# Main.net
KiCad netlist of a schematic drawn in Altium Designer
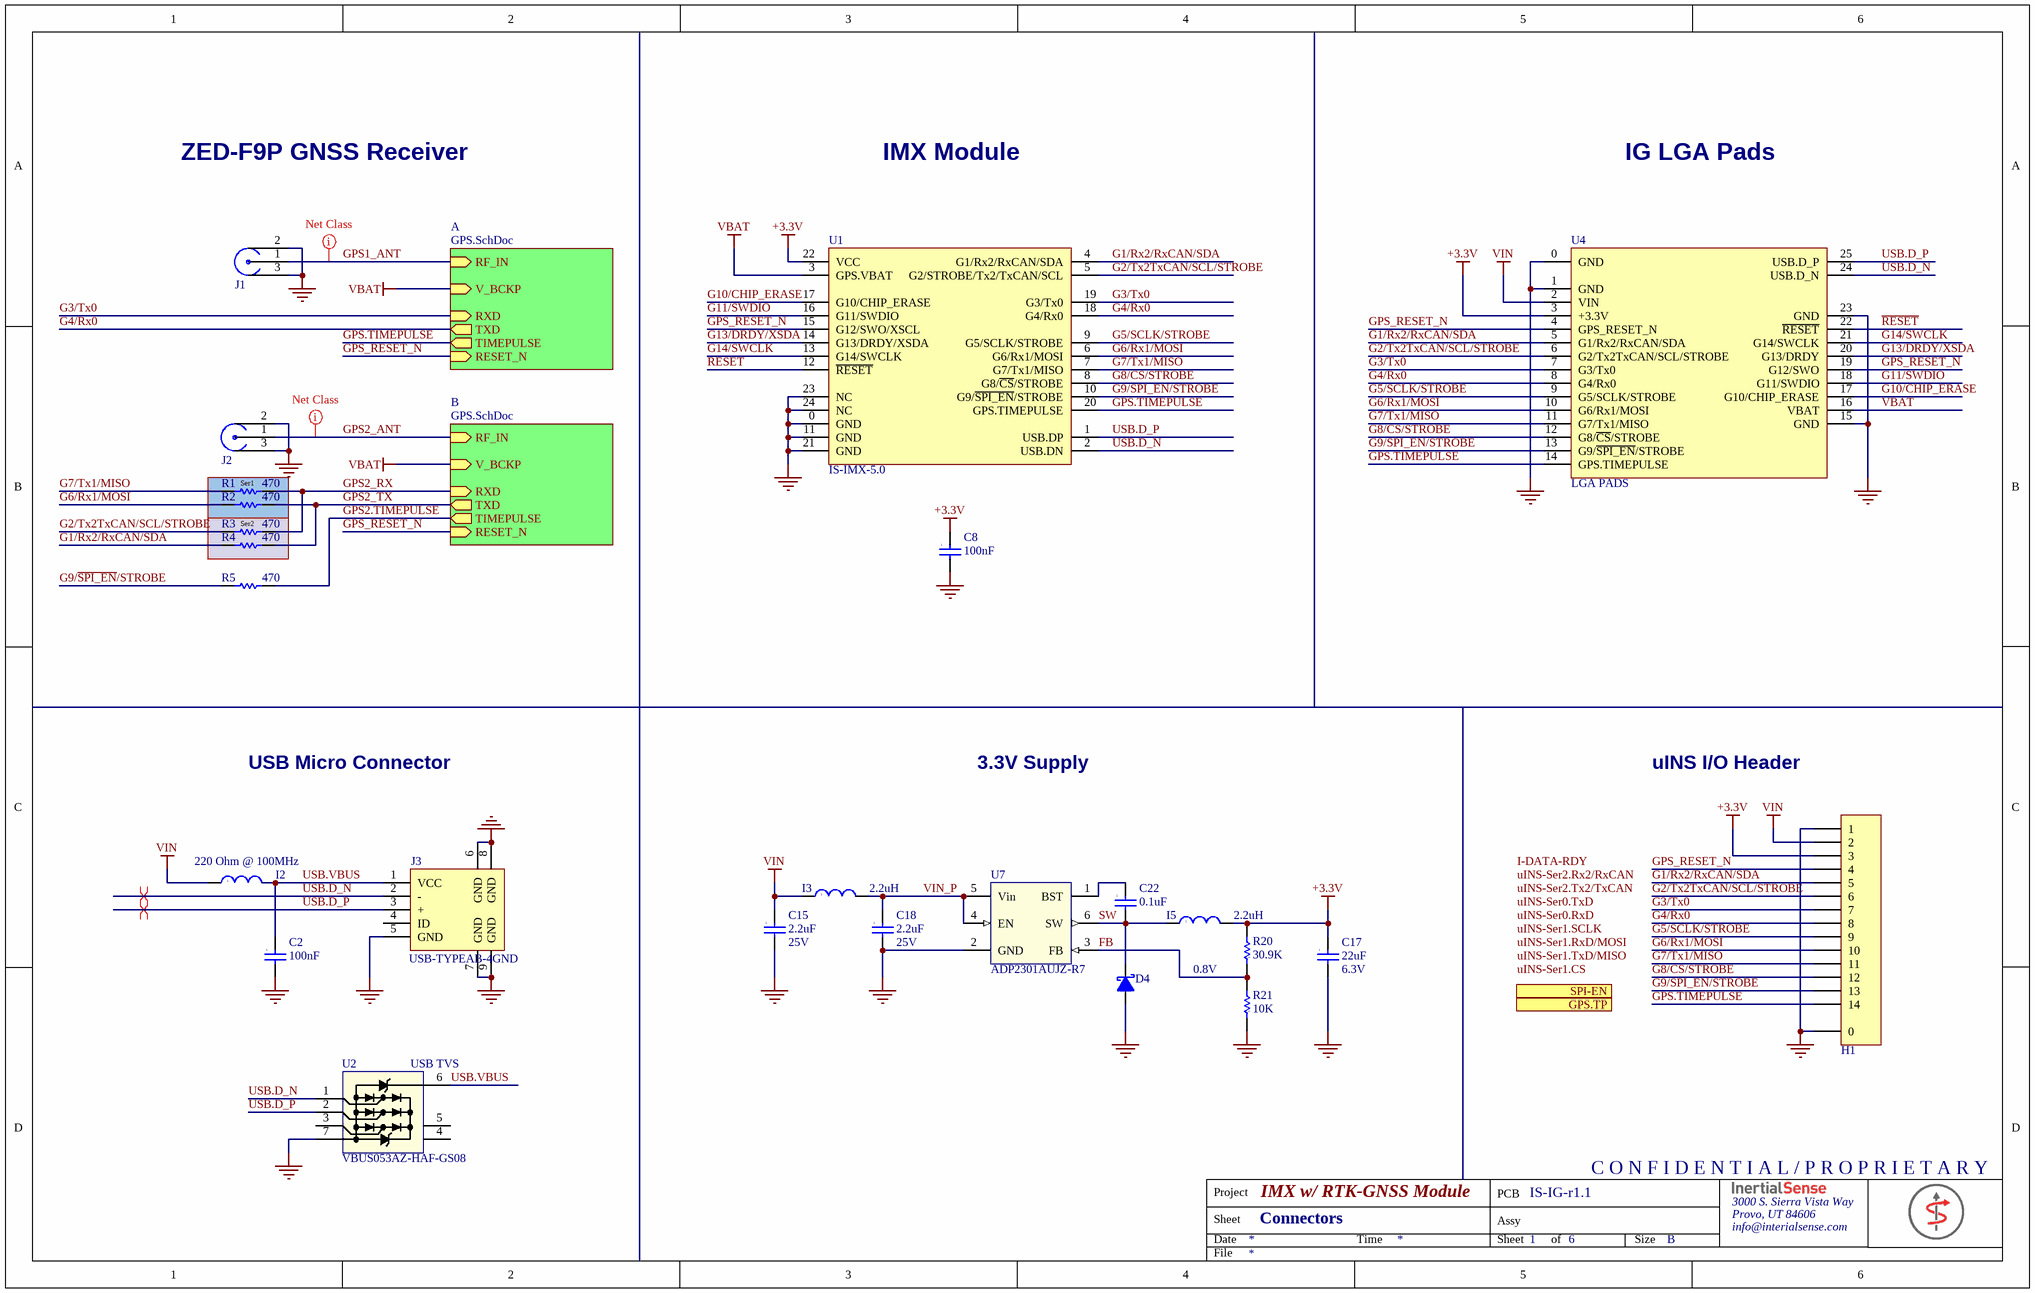
[diagram p0: Main.SchDoc]

(export (version "E")
  (design (tool "Eeschema 10.0.6"))
  (components
    (comp (ref "C2")
      (value "100nF")
      (footprint "0402")
      (description "CAP CER .10UF 50V X7R 10% 0402")
      (fields
        (field (name "MANUFACTURER") "TDK Corporation")
        (field (name "MANUFACTURER PART NUMBER") "C1005X7R1H104K")
        (field (name "PUBLISHER") "Altium Limited")
      )
      (libsource (lib "General") (part "Cap"))
    )
    (comp (ref "C8")
      (value "100nF")
      (footprint "0402")
      (description "CAP CER .10UF 50V X7R 10% 0402")
      (fields
        (field (name "MANUFACTURER") "TDK Corporation")
        (field (name "MANUFACTURER PART NUMBER") "C1005X7R1H104K")
        (field (name "PUBLISHER") "Altium Limited")
      )
      (libsource (lib "General") (part "Cap"))
    )
    (comp (ref "C15")
      (value "2.2uF")
      (footprint "0603")
      (description "CAP CER 2.2UF 25V X6S 0603")
      (fields
        (field (name "MANUFACTURER") "Murata")
        (field (name "MANUFACTURER PART NUMBER") "GRT188C81E225KE13D")
        (field (name "VOLTAGE RATING") "25V")
        (field (name "PUBLISHER") "Altium Limited")
      )
      (libsource (lib "") (part "Cap_1"))
    )
    (comp (ref "C17")
      (value "22uF")
      (footprint "0603")
      (description "CAP CER 22UF 6.3V X6S 0603")
      (fields
        (field (name "MANUFACTURER") "Murata")
        (field (name "MANUFACTURER PART NUMBER") "GRM188C80J226ME15D")
        (field (name "VOLTAGE RATING") "6.3V")
        (field (name "PUBLISHER") "Altium Limited")
      )
      (libsource (lib "") (part "Cap_1"))
    )
    (comp (ref "C18")
      (value "2.2uF")
      (footprint "0603")
      (description "CAP CER 2.2UF 25V X6S 0603")
      (fields
        (field (name "MANUFACTURER") "Murata")
        (field (name "MANUFACTURER PART NUMBER") "GRT188C81E225KE13D")
        (field (name "VOLTAGE RATING") "25V")
        (field (name "PUBLISHER") "Altium Limited")
      )
      (libsource (lib "") (part "Cap_1"))
    )
    (comp (ref "C22")
      (value "0.1uF")
      (footprint "0402")
      (description "CAP CER 0.1UF 50V X7R 0402")
      (fields
        (field (name "MANUFACTURER") "TDK")
        (field (name "MANUFACTURER PART NUMBER") "CGA2B3X7R1H104K050BB")
        (field (name "PUBLISHER") "Altium Limited")
      )
      (libsource (lib "") (part "Cap_1"))
    )
    (comp (ref "D4")
      (value "Diode - Schottky")
      (footprint "D0603B")
      (description "DIODE SCHOTTKY 30V 2A 0603")
      (fields
        (field (name "MANUFACTURER") "Vishay")
        (field (name "MANUFACTURER PART NUMBER") "VSKY20301608-G4-08")
      )
      (libsource (lib "General") (part "Diode - Schottky"))
    )
    (comp (ref "H1")
      (value "Hdr - 14pin - mount")
      (footprint "SM14B-GHS-TB(LF)(SN)")
      (description "Conn Shrouded Header HDR 14 POS 1.25mm Solder ST Top Entry SMD T/R")
      (fields
        (field (name "MANUFACTURER") "JST")
        (field (name "MANUFACTURER PART NUMBER") "SM14B-GHS-TB(LF)(SN)")
      )
      (libsource (lib "Connectors") (part "Hdr - 14pin - mount"))
    )
    (comp (ref "I2")
      (value "220 Ohm @ 100MHz")
      (footprint "I0603")
      (description "FERRITE CHIP 220 OHM 2500MA 0603")
      (fields
        (field (name "MANUFACTURER") "Murata Electronics North America")
        (field (name "MANUFACTURER PART NUMBER") "BLM18SG221TN1D")
      )
      (libsource (lib "General") (part "Inductor"))
    )
    (comp (ref "I3")
      (value "2.2uH")
      (footprint "0806")
      (description "FIXED IND 2.2UH 1.2A 110 MOHM")
      (fields
        (field (name "MANUFACTURER") "TDK")
        (field (name "MANUFACTURER PART NUMBER") "MLP2016H2R2MT0S1")
      )
      (libsource (lib "") (part "Inductor_1"))
    )
    (comp (ref "I5")
      (value "2.2uH")
      (footprint "0806")
      (description "FIXED IND 2.2UH 1.2A 110 MOHM")
      (fields
        (field (name "MANUFACTURER") "TDK")
        (field (name "MANUFACTURER PART NUMBER") "MLP2016H2R2MT0S1")
      )
      (libsource (lib "") (part "Inductor_1"))
    )
    (comp (ref "J1")
      (value "RF - GND x 2")
      (footprint "RF UMC SMD")
      (description "CONN UMC RCPT STR 50 OHM SMD")
      (fields
        (field (name "MANUFACTURER") "Emerson Network Power Connectivity Johnson")
        (field (name "MANUFACTURER PART NUMBER") "128-0711-201")
      )
      (libsource (lib "Connectors") (part "RF - GND x 2"))
    )
    (comp (ref "J2")
      (value "RF - GND x 2")
      (footprint "RF UMC SMD")
      (description "CONN UMC RCPT STR 50 OHM SMD")
      (fields
        (field (name "MANUFACTURER") "Emerson Network Power Connectivity Johnson")
        (field (name "MANUFACTURER PART NUMBER") "128-0711-201")
      )
      (libsource (lib "Connectors") (part "RF - GND x 2"))
    )
    (comp (ref "J3")
      (value "USB-TYPEAB-4GND")
      (footprint "USB Micro AB R/A THR")
      (description "CONN USB AB 4POS")
      (fields
        (field (name "MANUFACTURER") "Amphenol FCI")
        (field (name "MANUFACTURER PART NUMBER") "10118194-0001LF")
      )
      (libsource (lib "Connectors") (part "USB-TYPEAB-4GND"))
    )
    (comp (ref "R1")
      (value "470")
      (footprint "R0402")
      (description "RES 470 OHM 1/16W 1% 0402 SMD")
      (fields
        (field (name "MANUFACTURER") "Vishay Dale")
        (field (name "MANUFACTURER PART NUMBER") "CRCW0402470RFKED")
      )
      (libsource (lib "") (part "Res_1"))
    )
    (comp (ref "R2")
      (value "470")
      (footprint "R0402")
      (description "RES 470 OHM 1/16W 1% 0402 SMD")
      (fields
        (field (name "MANUFACTURER") "Vishay Dale")
        (field (name "MANUFACTURER PART NUMBER") "CRCW0402470RFKED")
      )
      (libsource (lib "") (part "Res_1"))
    )
    (comp (ref "R3")
      (value "470")
      (footprint "R0402")
      (description "RES 470 OHM 1/16W 1% 0402 SMD")
      (fields
        (field (name "MANUFACTURER") "Vishay Dale")
        (field (name "MANUFACTURER PART NUMBER") "CRCW0402470RFKED")
      )
      (libsource (lib "") (part "Res_1"))
    )
    (comp (ref "R4")
      (value "470")
      (footprint "R0402")
      (description "RES 470 OHM 1/16W 1% 0402 SMD")
      (fields
        (field (name "MANUFACTURER") "Vishay Dale")
        (field (name "MANUFACTURER PART NUMBER") "CRCW0402470RFKED")
      )
      (libsource (lib "") (part "Res_1"))
    )
    (comp (ref "R5")
      (value "470")
      (footprint "R0402")
      (description "RES 470 OHM 1/16W 1% 0402 SMD")
      (fields
        (field (name "MANUFACTURER") "Vishay Dale")
        (field (name "MANUFACTURER PART NUMBER") "CRCW0402470RFKED")
      )
      (libsource (lib "") (part "Res_1"))
    )
    (comp (ref "R20")
      (value "30.9K")
      (footprint "R0402")
      (description "RES TF 30.9K OHM 1% 1/16W 0402")
      (fields
        (field (name "MANUFACTURER") "Stackpole Electronics Inc")
        (field (name "MANUFACTURER PART NUMBER") "RMCF0402FT30K9")
      )
      (libsource (lib "General") (part "Res"))
    )
    (comp (ref "R21")
      (value "10K")
      (footprint "R0402")
      (description "RES 10.0K OHM 1/16W 1% 0402 SMD")
      (fields
        (field (name "MANUFACTURER") "Yageo")
        (field (name "MANUFACTURER PART NUMBER") "RC0402FR-0710KL")
      )
      (libsource (lib "General") (part "Res"))
    )
    (comp (ref "U1")
      (value "IMX")
      (footprint "IS-IMX-5.0")
      (description "Inertial Sense IMX")
      (fields
        (field (name "MANUFACTURER") "Inertial Sense")
        (field (name "MANUFACTURER PART NUMBER") "IS-IMX-5.0")
      )
      (libsource (lib "IS-IMX-5") (part "IS-IMX-5.0"))
    )
    (comp (ref "U2")
      (value "VBUS053")
      (footprint "QFN50P160X160X60-6N")
      (description "ESD SUPPRESS 5.5V 36W 3-Line USB")
      (fields
        (field (name "MANUFACTURER") "Vishay Semiconductors")
        (field (name "MANUFACTURER PART NUMBER") "VBUS053AZ-HAF-GS08")
      )
      (libsource (lib "ICs") (part "VBUS053"))
    )
    (comp (ref "U4")
      (value "LGA PADS")
      (footprint "IG-1.0_LGA")
      (description "IMX multi-frequency RTK-GNSS Module")
      (libsource (lib "Sensors") (part "IG_1.0_LGA"))
    )
    (comp (ref "U7")
      (value "ADP2301")
      (footprint "MO-178-AB")
      (description "IC BUCK ADJ 1.2A 6TSOT")
      (fields
        (field (name "MANUFACTURER") "Analog Devices Inc")
        (field (name "MANUFACTURER PART NUMBER") "ADP2301AUJZ-R7")
      )
      (libsource (lib "ICs") (part "ADP2301"))
    )
  )
  (nets
    (net (code "1") (name "+3.3V") (class "Default")
      (node (ref "C17") (pin "1") (pinfunction "1_1") (pintype "passive"))
      (node (ref "C8") (pin "1") (pinfunction "1_1") (pintype "passive"))
      (node (ref "H1") (pin "3") (pinfunction "3_3") (pintype "passive"))
      (node (ref "I5") (pin "2") (pinfunction "2_2") (pintype "passive"))
      (node (ref "R20") (pin "2") (pinfunction "2_2") (pintype "passive"))
      (node (ref "U1") (pin "22") (pinfunction "VCC_22") (pintype "power_in"))
      (node (ref "U4") (pin "3") (pinfunction "+3.3V_3") (pintype "passive"))
    )
    (net (code "2") (name "/FB") (class "Default")
      (node (ref "R20") (pin "1") (pinfunction "1_1") (pintype "passive"))
      (node (ref "R21") (pin "2") (pinfunction "2_2") (pintype "passive"))
      (node (ref "U7") (pin "3") (pinfunction "FB_3") (pintype "input"))
    )
    (net (code "3") (name "/G1{slash}Rx2{slash}RxCAN{slash}SDA") (class "Default")
      (node (ref "H1") (pin "5") (pinfunction "5_5") (pintype "passive"))
      (node (ref "R4") (pin "1") (pinfunction "1_1") (pintype "passive"))
      (node (ref "U1") (pin "4") (pinfunction "G1/Rx2/RxCAN/SDA_4") (pintype "passive"))
      (node (ref "U4") (pin "5") (pinfunction "G1/Rx2/RxCAN/SDA_5") (pintype "passive"))
    )
    (net (code "4") (name "/G2{slash}Tx2TxCAN{slash}SCL{slash}STROBE") (class "Default")
      (node (ref "H1") (pin "6") (pinfunction "6_6") (pintype "passive"))
      (node (ref "R3") (pin "1") (pinfunction "1_1") (pintype "passive"))
      (node (ref "U1") (pin "5") (pinfunction "G2/STROBE/Tx2/TxCAN/SCL_5") (pintype "passive"))
      (node (ref "U4") (pin "6") (pinfunction "G2/Tx2TxCAN/SCL/STROBE_6") (pintype "passive"))
    )
    (net (code "5") (name "/G3{slash}Tx0") (class "Default")
      (node (ref "H1") (pin "7") (pinfunction "7_7") (pintype "passive"))
      (node (ref "U1") (pin "19") (pinfunction "G3/Tx0_19") (pintype "passive"))
      (node (ref "U4") (pin "7") (pinfunction "G3/Tx0_7") (pintype "passive"))
    )
    (net (code "6") (name "/G4{slash}Rx0") (class "Default")
      (node (ref "H1") (pin "8") (pinfunction "8_8") (pintype "passive"))
      (node (ref "U1") (pin "18") (pinfunction "G4/Rx0_18") (pintype "passive"))
      (node (ref "U4") (pin "8") (pinfunction "G4/Rx0_8") (pintype "passive"))
    )
    (net (code "7") (name "/G5{slash}SCLK{slash}STROBE") (class "Default")
      (node (ref "H1") (pin "9") (pinfunction "9_9") (pintype "passive"))
      (node (ref "U1") (pin "9") (pinfunction "G5/SCLK/STROBE_9") (pintype "passive"))
      (node (ref "U4") (pin "9") (pinfunction "G5/SCLK/STROBE_9") (pintype "passive"))
    )
    (net (code "8") (name "/G6{slash}Rx1{slash}MOSI") (class "Default")
      (node (ref "H1") (pin "10") (pinfunction "10_10") (pintype "passive"))
      (node (ref "R2") (pin "1") (pinfunction "1_1") (pintype "passive"))
      (node (ref "U1") (pin "6") (pinfunction "G6/Rx1/MOSI_6") (pintype "passive"))
      (node (ref "U4") (pin "10") (pinfunction "G6/Rx1/MOSI_10") (pintype "passive"))
    )
    (net (code "9") (name "/G7{slash}Tx1{slash}MISO") (class "Default")
      (node (ref "H1") (pin "11") (pinfunction "11_11") (pintype "passive"))
      (node (ref "R1") (pin "1") (pinfunction "1_1") (pintype "passive"))
      (node (ref "U1") (pin "7") (pinfunction "G7/Tx1/MISO_7") (pintype "passive"))
      (node (ref "U4") (pin "11") (pinfunction "G7/Tx1/MISO_11") (pintype "passive"))
    )
    (net (code "10") (name "/G8{slash}~{CS}{slash}STROBE") (class "Default")
      (node (ref "H1") (pin "12") (pinfunction "12_12") (pintype "passive"))
      (node (ref "U1") (pin "8") (pinfunction "G8/~{CS}/STROBE_8") (pintype "passive"))
      (node (ref "U4") (pin "12") (pinfunction "G8/~{CS}/STROBE_12") (pintype "passive"))
    )
    (net (code "11") (name "/G9{slash}~{SPI_EN}{slash}STROBE") (class "Default")
      (node (ref "H1") (pin "13") (pinfunction "13_13") (pintype "passive"))
      (node (ref "R5") (pin "1") (pinfunction "1_1") (pintype "passive"))
      (node (ref "U1") (pin "10") (pinfunction "G9/~{SPI_EN}/STROBE_10") (pintype "passive"))
      (node (ref "U4") (pin "13") (pinfunction "G9/~{SPI_EN}/STROBE_13") (pintype "passive"))
    )
    (net (code "12") (name "/G10{slash}CHIP_ERASE") (class "Default")
      (node (ref "U1") (pin "17") (pinfunction "G10/CHIP_ERASE_17") (pintype "passive"))
      (node (ref "U4") (pin "17") (pinfunction "G10/CHIP_ERASE_17") (pintype "passive"))
    )
    (net (code "13") (name "/G11{slash}SWDIO") (class "Default")
      (node (ref "U1") (pin "16") (pinfunction "G11/SWDIO_16") (pintype "passive"))
      (node (ref "U4") (pin "18") (pinfunction "G11/SWDIO_18") (pintype "passive"))
    )
    (net (code "14") (name "/G13{slash}DRDY{slash}XSDA") (class "Default")
      (node (ref "U1") (pin "14") (pinfunction "G13/DRDY/XSDA_14") (pintype "passive"))
      (node (ref "U4") (pin "20") (pinfunction "G13/DRDY_20") (pintype "passive"))
    )
    (net (code "15") (name "/G14{slash}SWCLK") (class "Default")
      (node (ref "U1") (pin "13") (pinfunction "G14/SWCLK_13") (pintype "passive"))
      (node (ref "U4") (pin "21") (pinfunction "G14/SWCLK_21") (pintype "passive"))
    )
    (net (code "16") (name "/GPS.TIMEPULSE") (class "Default")
      (node (ref "H1") (pin "14") (pinfunction "14_14") (pintype "passive"))
      (node (ref "U1") (pin "20") (pinfunction "GPS.TIMEPULSE_20") (pintype "passive"))
      (node (ref "U4") (pin "14") (pinfunction "GPS.TIMEPULSE_14") (pintype "passive"))
    )
    (net (code "18") (name "/GPS1_ANT") (class "Default")
      (node (ref "J1") (pin "1") (pinfunction "1_1") (pintype "passive"))
    )
    (net (code "19") (name "/GPS2.TIMEPULSE") (class "Default")
      (node (ref "R5") (pin "2") (pinfunction "2_2") (pintype "passive"))
    )
    (net (code "20") (name "/GPS2_ANT") (class "Default")
      (node (ref "J2") (pin "1") (pinfunction "1_1") (pintype "passive"))
    )
    (net (code "21") (name "/GPS2_RX") (class "Default")
      (node (ref "R1") (pin "2") (pinfunction "2_2") (pintype "passive"))
      (node (ref "R3") (pin "2") (pinfunction "2_2") (pintype "passive"))
    )
    (net (code "22") (name "/GPS2_TX") (class "Default")
      (node (ref "R2") (pin "2") (pinfunction "2_2") (pintype "passive"))
      (node (ref "R4") (pin "2") (pinfunction "2_2") (pintype "passive"))
    )
    (net (code "23") (name "/GPS_RESET_N") (class "Default")
      (node (ref "H1") (pin "4") (pinfunction "4_4") (pintype "passive"))
      (node (ref "U1") (pin "15") (pinfunction "G12/SWO/XSCL_15") (pintype "passive"))
      (node (ref "U4") (pin "19") (pinfunction "G12/SWO_19") (pintype "passive"))
      (node (ref "U4") (pin "4") (pinfunction "GPS_RESET_N_4") (pintype "passive"))
    )
    (net (code "25") (name "/RESET") (class "Default")
      (node (ref "U1") (pin "12") (pinfunction "~{RESET}_12") (pintype "passive"))
      (node (ref "U4") (pin "22") (pinfunction "~{RESET}_22") (pintype "passive"))
    )
    (net (code "27") (name "/SW") (class "Default")
      (node (ref "C22") (pin "2") (pinfunction "2_2") (pintype "passive"))
      (node (ref "D4") (pin "C") (pinfunction "C_C") (pintype "passive"))
      (node (ref "I5") (pin "1") (pinfunction "1_1") (pintype "passive"))
      (node (ref "U7") (pin "6") (pinfunction "SW_6") (pintype "output"))
    )
    (net (code "28") (name "/USB.D_N") (class "Default")
      (node (ref "J3") (pin "2") (pinfunction "-_2") (pintype "passive"))
      (node (ref "U1") (pin "2") (pinfunction "USB.DN_2") (pintype "passive"))
      (node (ref "U2") (pin "1") (pintype "passive"))
      (node (ref "U4") (pin "24") (pinfunction "USB.D_N_24") (pintype "passive"))
    )
    (net (code "29") (name "/USB.D_P") (class "Default")
      (node (ref "J3") (pin "3") (pinfunction "+_3") (pintype "passive"))
      (node (ref "U1") (pin "1") (pinfunction "USB.DP_1") (pintype "passive"))
      (node (ref "U2") (pin "2") (pintype "passive"))
      (node (ref "U4") (pin "25") (pinfunction "USB.D_P_25") (pintype "passive"))
    )
    (net (code "30") (name "/USB.VBUS") (class "Default")
      (node (ref "C2") (pin "1") (pinfunction "1_1") (pintype "passive"))
      (node (ref "I2") (pin "2") (pinfunction "2_2") (pintype "passive"))
      (node (ref "J3") (pin "1") (pinfunction "VCC_1") (pintype "passive"))
      (node (ref "U2") (pin "6") (pintype "passive"))
    )
    (net (code "31") (name "/VIN_P") (class "Default")
      (node (ref "C18") (pin "1") (pinfunction "1_1") (pintype "passive"))
      (node (ref "I3") (pin "2") (pinfunction "2_2") (pintype "passive"))
      (node (ref "U7") (pin "4") (pinfunction "EN_4") (pintype "input"))
      (node (ref "U7") (pin "5") (pinfunction "Vin_5") (pintype "power_in"))
    )
    (net (code "40") (name "GND") (class "Default")
      (node (ref "C15") (pin "2") (pinfunction "2_2") (pintype "passive"))
      (node (ref "C17") (pin "2") (pinfunction "2_2") (pintype "passive"))
      (node (ref "C18") (pin "2") (pinfunction "2_2") (pintype "passive"))
      (node (ref "C2") (pin "2") (pinfunction "2_2") (pintype "passive"))
      (node (ref "C8") (pin "2") (pinfunction "2_2") (pintype "passive"))
      (node (ref "D4") (pin "A") (pinfunction "A_A") (pintype "passive"))
      (node (ref "H1") (pin "0") (pinfunction "0_0") (pintype "passive"))
      (node (ref "H1") (pin "1") (pinfunction "1_1") (pintype "passive"))
      (node (ref "J1") (pin "2") (pinfunction "2_2") (pintype "passive"))
      (node (ref "J1") (pin "3") (pinfunction "3_3") (pintype "passive"))
      (node (ref "J2") (pin "2") (pinfunction "2_2") (pintype "passive"))
      (node (ref "J2") (pin "3") (pinfunction "3_3") (pintype "passive"))
      (node (ref "J3") (pin "5") (pinfunction "GND_5") (pintype "passive"))
      (node (ref "J3") (pin "6") (pinfunction "GND_6") (pintype "passive"))
      (node (ref "J3") (pin "7") (pinfunction "GND_7") (pintype "passive"))
      (node (ref "J3") (pin "8") (pinfunction "GND_8") (pintype "passive"))
      (node (ref "J3") (pin "9") (pinfunction "GND_9") (pintype "passive"))
      (node (ref "R21") (pin "1") (pinfunction "1_1") (pintype "passive"))
      (node (ref "U1") (pin "0") (pinfunction "GND_0") (pintype "power_in"))
      (node (ref "U1") (pin "11") (pinfunction "GND_11") (pintype "power_in"))
      (node (ref "U1") (pin "21") (pinfunction "GND_21") (pintype "power_in"))
      (node (ref "U1") (pin "23") (pinfunction "NC_23") (pintype "power_in"))
      (node (ref "U1") (pin "24") (pinfunction "NC_24") (pintype "power_in"))
      (node (ref "U2") (pin "7") (pintype "passive"))
      (node (ref "U4") (pin "0") (pinfunction "GND_0") (pintype "passive"))
      (node (ref "U4") (pin "1") (pinfunction "GND_1") (pintype "passive"))
      (node (ref "U4") (pin "15") (pinfunction "GND_15") (pintype "passive"))
      (node (ref "U4") (pin "23") (pinfunction "GND_23") (pintype "passive"))
      (node (ref "U7") (pin "2") (pinfunction "GND_2") (pintype "power_in"))
    )
    (net (code "41") (name "Net-(U7-BST)") (class "Default")
      (node (ref "C22") (pin "1") (pinfunction "1_1") (pintype "passive"))
      (node (ref "U7") (pin "1") (pinfunction "BST_1") (pintype "passive"))
    )
    (net (code "42") (name "VBAT") (class "Default")
      (node (ref "U1") (pin "3") (pinfunction "GPS.VBAT_3") (pintype "passive"))
      (node (ref "U4") (pin "16") (pinfunction "VBAT_16") (pintype "passive"))
    )
    (net (code "43") (name "VIN") (class "Default")
      (node (ref "C15") (pin "1") (pinfunction "1_1") (pintype "passive"))
      (node (ref "H1") (pin "2") (pinfunction "2_2") (pintype "passive"))
      (node (ref "I2") (pin "1") (pinfunction "1_1") (pintype "passive"))
      (node (ref "I3") (pin "1") (pinfunction "1_1") (pintype "passive"))
      (node (ref "U4") (pin "2") (pinfunction "VIN_2") (pintype "passive"))
    )
    (net (code "44") (name "unconnected-(J3-ID-Pad4)") (class "Default")
      (node (ref "J3") (pin "4") (pinfunction "ID_4") (pintype "passive"))
    )
    (net (code "45") (name "unconnected-(U2-Pad3)") (class "Default")
      (node (ref "U2") (pin "3") (pintype "passive"))
    )
    (net (code "46") (name "unconnected-(U2-nc-Pad4)") (class "Default")
      (node (ref "U2") (pin "4") (pinfunction "nc_4") (pintype "passive"))
    )
    (net (code "47") (name "unconnected-(U2-nc-Pad5)") (class "Default")
      (node (ref "U2") (pin "5") (pinfunction "nc_5") (pintype "passive"))
    )
  )
)
